# main_flight_computer.net
KiCad netlist of a schematic drawn in EAGLE
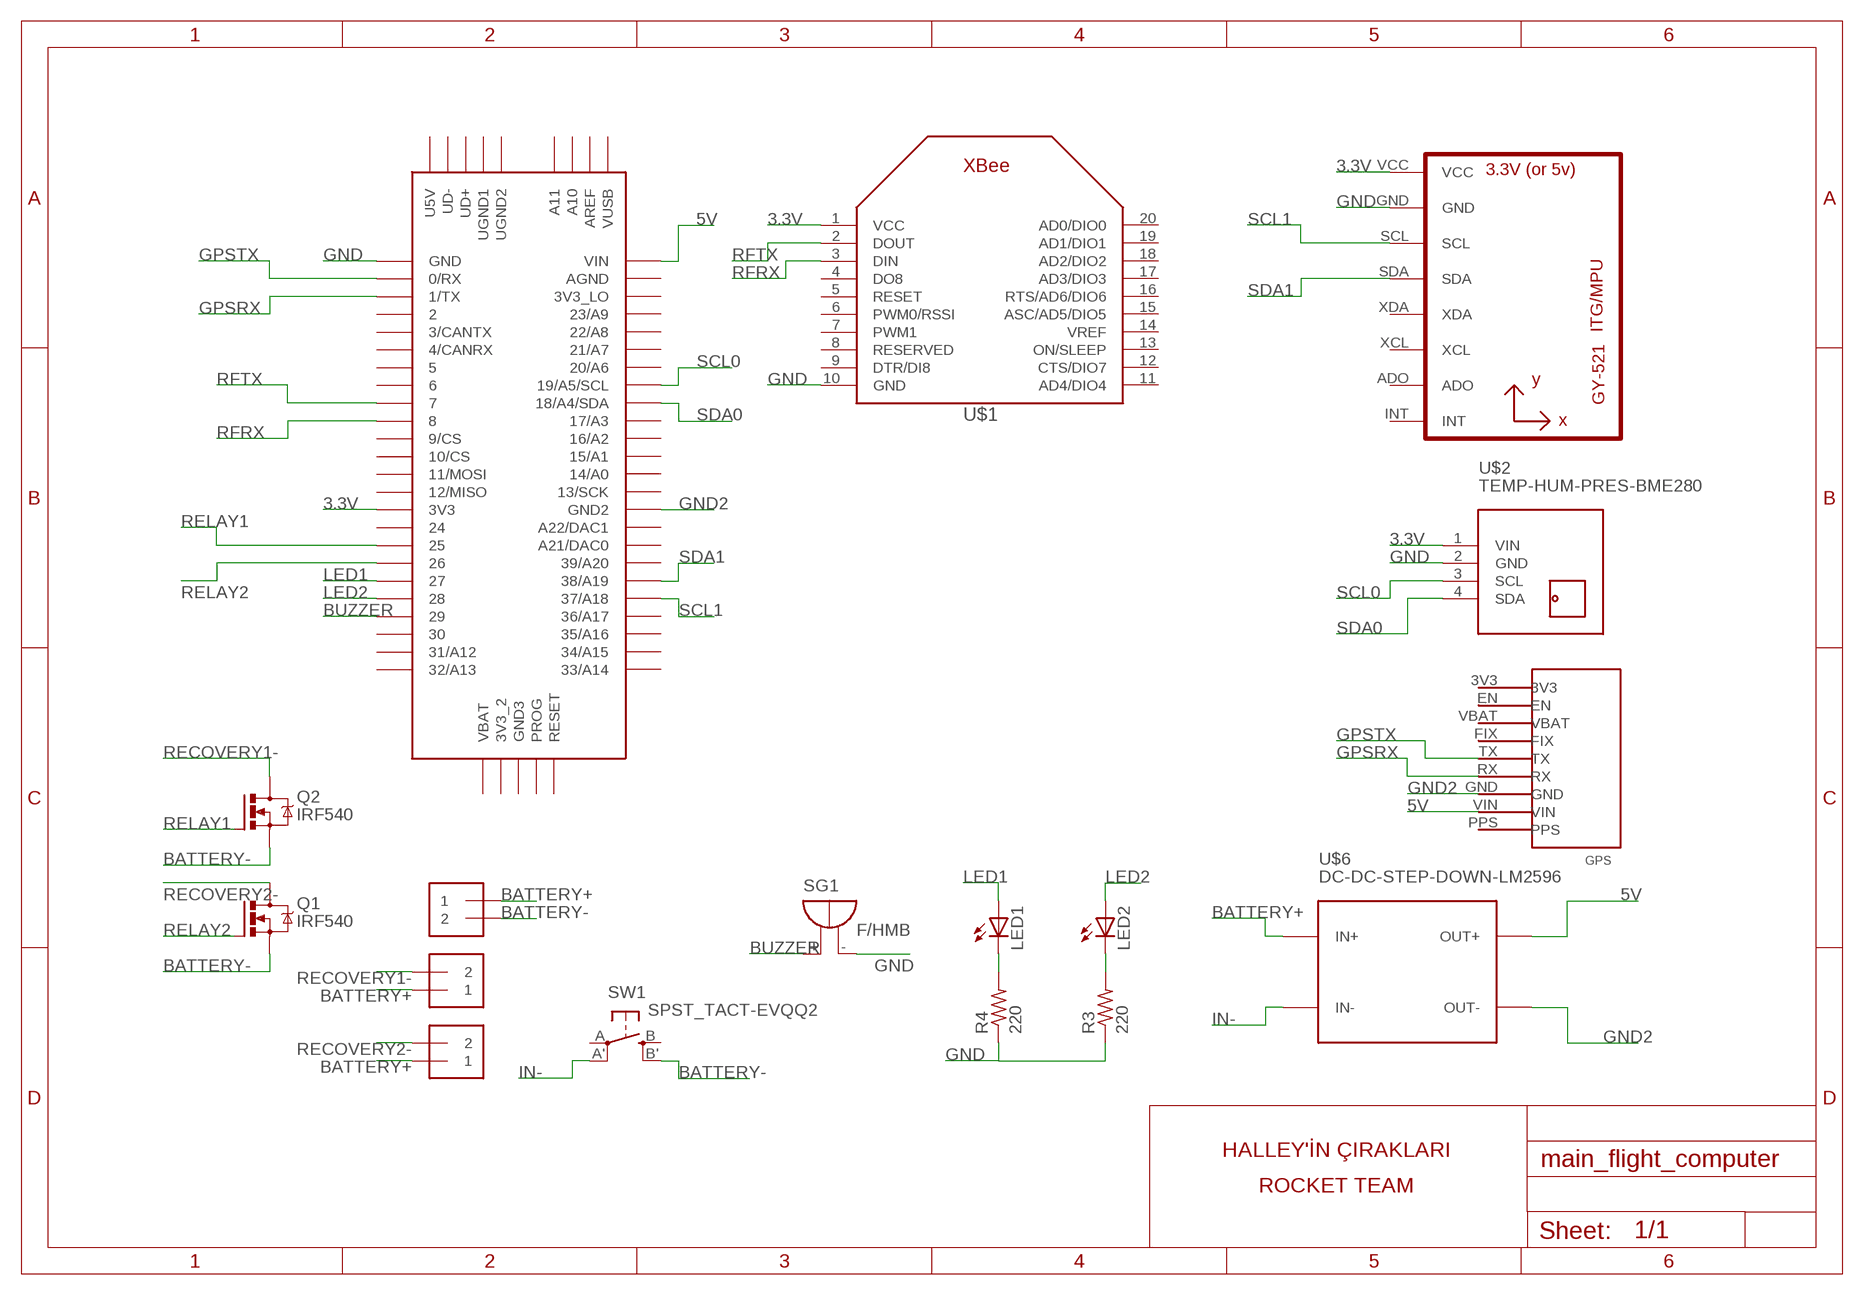
[diagram p0: schematic, sheet 1]

(export (version "E")
  (design (tool "Eeschema 10.0.6"))
  (components
    (comp (ref "J1")
      (value "1X2-3.5MM")
      (footprint "eagle-import:1X2-3.5MM")
      (libsource (lib "eagle-import") (part "1X2-3.5MM"))
    )
    (comp (ref "J2")
      (value "1X2-3.5MM")
      (footprint "eagle-import:1X2-3.5MM")
      (libsource (lib "eagle-import") (part "1X2-3.5MM"))
    )
    (comp (ref "J3")
      (value "1X2-3.5MM")
      (footprint "eagle-import:1X2-3.5MM")
      (libsource (lib "eagle-import") (part "1X2-3.5MM"))
    )
    (comp (ref "LED1")
      (value "LED5MM")
      (footprint "eagle-import:LED5MM")
      (libsource (lib "eagle-import") (part "LED5MM"))
    )
    (comp (ref "LED2")
      (value "LED5MM")
      (footprint "eagle-import:LED5MM")
      (libsource (lib "eagle-import") (part "LED5MM"))
    )
    (comp (ref "Q1")
      (value "IRF540")
      (footprint "eagle-import:TO220BV")
      (fields (field (name "MANUFACTURER") "Infineon Technologies") (field (name "MPN") "IRF540NPBF"))
      (libsource (lib "eagle-import") (part "NMOSFET_-TO220IRF540"))
    )
    (comp (ref "Q2")
      (value "IRF540")
      (footprint "eagle-import:TO220BV")
      (fields (field (name "MANUFACTURER") "Infineon Technologies") (field (name "MPN") "IRF540NPBF"))
      (libsource (lib "eagle-import") (part "NMOSFET_-TO220IRF540"))
    )
    (comp (ref "R3")
      (value "220")
      (footprint "eagle-import:0204_7")
      (libsource (lib "eagle-import") (part "R-US_0204/7"))
    )
    (comp (ref "R4")
      (value "220")
      (footprint "eagle-import:0204_7")
      (libsource (lib "eagle-import") (part "R-US_0204/7"))
    )
    (comp (ref "SG1")
      (value "F/HMB")
      (footprint "eagle-import:F_HMB")
      (libsource (lib "eagle-import") (part "F/HMB"))
    )
    (comp (ref "SW1")
      (value "SPST_TACT-EVQQ2")
      (footprint "eagle-import:EVQ-Q2")
      (libsource (lib "eagle-import") (part "SPST_TACT-EVQQ2"))
    )
    (comp (ref "U$1")
      (value "XBEE")
      (footprint "eagle-import:XBEE")
      (libsource (lib "eagle-import") (part "XBEE"))
    )
    (comp (ref "U$2")
      (value "TEMP-HUM-PRES-BME280")
      (footprint "eagle-import:TEMP-HUM-PRES-BME280")
      (libsource (lib "eagle-import") (part "TEMP-HUM-PRES-BME280"))
    )
    (comp (ref "U$3")
      (value "TEENSY_3.5/3.6")
      (footprint "eagle-import:TEENSY_3.5_3.6")
      (libsource (lib "eagle-import") (part "TEENSY_3.5/3.6"))
    )
    (comp (ref "U$5")
      (value "GPS")
      (footprint "eagle-import:GPS")
      (libsource (lib "eagle-import") (part "GPS"))
    )
    (comp (ref "U$6")
      (value "DC-DC-STEP-DOWN-LM2596")
      (footprint "eagle-import:DC-DC-STEP-DOWN-LM2596")
      (libsource (lib "eagle-import") (part "DC-DC-STEP-DOWN-LM2596"))
    )
    (comp (ref "U1")
      (value "GY-521MPU6050")
      (footprint "eagle-import:GY-521")
      (libsource (lib "eagle-import") (part "GY-521MPU6050"))
    )
  )
  (nets
    (net (code "1") (name "/3.3V") (class "Default")
      (node (ref "U$1") (pin "1") (pinfunction "VCC_1") (pintype "power_in"))
      (node (ref "U$2") (pin "1") (pinfunction "VIN_1") (pintype "power_in"))
      (node (ref "U$3") (pin "3V3") (pinfunction "3V3_3V3") (pintype "bidirectional"))
      (node (ref "U1") (pin "VCC") (pinfunction "VCC_VCC") (pintype "bidirectional"))
    )
    (net (code "2") (name "/5V") (class "Default")
      (node (ref "U$3") (pin "VIN") (pinfunction "VIN_VIN") (pintype "bidirectional"))
      (node (ref "U$5") (pin "VIN") (pinfunction "VIN_VIN") (pintype "bidirectional"))
      (node (ref "U$6") (pin "OUT+") (pinfunction "OUT+_OUT+") (pintype "bidirectional"))
    )
    (net (code "3") (name "/BATTERY+") (class "Default")
      (node (ref "J1") (pin "1") (pinfunction "1_1") (pintype "passive"))
      (node (ref "J2") (pin "1") (pinfunction "1_1") (pintype "passive"))
      (node (ref "J3") (pin "1") (pinfunction "1_1") (pintype "passive"))
      (node (ref "U$6") (pin "IN+") (pinfunction "IN+_IN+") (pintype "bidirectional"))
    )
    (net (code "4") (name "/BATTERY-") (class "Default")
      (node (ref "J1") (pin "2") (pinfunction "2_2") (pintype "passive"))
      (node (ref "Q1") (pin "S") (pinfunction "S_S") (pintype "passive"))
      (node (ref "Q2") (pin "S") (pinfunction "S_S") (pintype "passive"))
      (node (ref "SW1") (pin "B'") (pinfunction "S1_B'") (pintype "passive"))
    )
    (net (code "5") (name "/BUZZER") (class "Default")
      (node (ref "SG1") (pin "+") (pinfunction "+_+") (pintype "passive"))
      (node (ref "U$3") (pin "29") (pinfunction "29_29") (pintype "bidirectional"))
    )
    (net (code "6") (name "/GND") (class "Default")
      (node (ref "R3") (pin "1") (pinfunction "1_1") (pintype "passive"))
      (node (ref "R4") (pin "1") (pinfunction "1_1") (pintype "passive"))
      (node (ref "SG1") (pin "-") (pinfunction "-_-") (pintype "passive"))
      (node (ref "U$1") (pin "10") (pinfunction "GND_10") (pintype "power_in"))
      (node (ref "U$2") (pin "2") (pinfunction "GND_2") (pintype "power_in"))
      (node (ref "U$3") (pin "GND") (pinfunction "GND_GND") (pintype "bidirectional"))
      (node (ref "U1") (pin "GND") (pinfunction "GND_GND") (pintype "bidirectional"))
    )
    (net (code "7") (name "/GND2") (class "Default")
      (node (ref "U$3") (pin "GND2") (pinfunction "GND2_GND2") (pintype "bidirectional"))
      (node (ref "U$5") (pin "GND") (pinfunction "GND_GND") (pintype "bidirectional"))
      (node (ref "U$6") (pin "OUT-") (pinfunction "OUT-_OUT-") (pintype "bidirectional"))
    )
    (net (code "8") (name "/GPSRX") (class "Default")
      (node (ref "U$3") (pin "1/TX") (pinfunction "1/TX_1/TX") (pintype "bidirectional"))
      (node (ref "U$5") (pin "RX") (pinfunction "RX_RX") (pintype "bidirectional"))
    )
    (net (code "9") (name "/GPSTX") (class "Default")
      (node (ref "U$3") (pin "0/RX") (pinfunction "0/RX_0/RX") (pintype "bidirectional"))
      (node (ref "U$5") (pin "TX") (pinfunction "TX_TX") (pintype "bidirectional"))
    )
    (net (code "10") (name "/IN-") (class "Default")
      (node (ref "SW1") (pin "A'") (pinfunction "P1_A'") (pintype "passive"))
      (node (ref "U$6") (pin "IN-") (pinfunction "IN-_IN-") (pintype "bidirectional"))
    )
    (net (code "11") (name "/LED1") (class "Default")
      (node (ref "LED1") (pin "A") (pinfunction "A_A") (pintype "passive"))
      (node (ref "U$3") (pin "27") (pinfunction "27_27") (pintype "bidirectional"))
    )
    (net (code "12") (name "/LED2") (class "Default")
      (node (ref "LED2") (pin "A") (pinfunction "A_A") (pintype "passive"))
      (node (ref "U$3") (pin "28") (pinfunction "28_28") (pintype "bidirectional"))
    )
    (net (code "13") (name "/RECOVERY1-") (class "Default")
      (node (ref "J2") (pin "2") (pinfunction "2_2") (pintype "passive"))
      (node (ref "Q2") (pin "D") (pinfunction "D_D") (pintype "passive"))
    )
    (net (code "14") (name "/RECOVERY2-") (class "Default")
      (node (ref "J3") (pin "2") (pinfunction "2_2") (pintype "passive"))
      (node (ref "Q1") (pin "D") (pinfunction "D_D") (pintype "passive"))
    )
    (net (code "15") (name "/RELAY1") (class "Default")
      (node (ref "Q2") (pin "G") (pinfunction "G_G") (pintype "passive"))
      (node (ref "U$3") (pin "25") (pinfunction "25_25") (pintype "bidirectional"))
    )
    (net (code "16") (name "/RELAY2") (class "Default")
      (node (ref "Q1") (pin "G") (pinfunction "G_G") (pintype "passive"))
      (node (ref "U$3") (pin "26") (pinfunction "26_26") (pintype "bidirectional"))
    )
    (net (code "17") (name "/RFRX") (class "Default")
      (node (ref "U$1") (pin "3") (pinfunction "DIN_3") (pintype "input"))
      (node (ref "U$3") (pin "8") (pinfunction "8_8") (pintype "bidirectional"))
    )
    (net (code "18") (name "/RFTX") (class "Default")
      (node (ref "U$1") (pin "2") (pinfunction "DOUT_2") (pintype "output"))
      (node (ref "U$3") (pin "7") (pinfunction "7_7") (pintype "bidirectional"))
    )
    (net (code "19") (name "/SCL0") (class "Default")
      (node (ref "U$2") (pin "3") (pinfunction "SCL_3") (pintype "bidirectional"))
      (node (ref "U$3") (pin "19/A5/SCL") (pinfunction "19/A5/SCL_19/A5/SCL") (pintype "bidirectional"))
    )
    (net (code "20") (name "/SCL1") (class "Default")
      (node (ref "U$3") (pin "37/A18") (pinfunction "37/A18_37/A18") (pintype "bidirectional"))
      (node (ref "U1") (pin "SCL") (pinfunction "SCL_SCL") (pintype "bidirectional"))
    )
    (net (code "21") (name "/SDA0") (class "Default")
      (node (ref "U$2") (pin "4") (pinfunction "SDA_4") (pintype "bidirectional"))
      (node (ref "U$3") (pin "18/A4/SDA") (pinfunction "18/A4/SDA_18/A4/SDA") (pintype "bidirectional"))
    )
    (net (code "22") (name "/SDA1") (class "Default")
      (node (ref "U$3") (pin "38/A19") (pinfunction "38/A19_38/A19") (pintype "bidirectional"))
      (node (ref "U1") (pin "SDA") (pinfunction "SDA_SDA") (pintype "bidirectional"))
    )
    (net (code "23") (name "Net-(LED1-C)") (class "Default")
      (node (ref "LED1") (pin "K") (pinfunction "C_K") (pintype "passive"))
      (node (ref "R4") (pin "2") (pinfunction "2_2") (pintype "passive"))
    )
    (net (code "24") (name "Net-(LED2-C)") (class "Default")
      (node (ref "LED2") (pin "K") (pinfunction "C_K") (pintype "passive"))
      (node (ref "R3") (pin "2") (pinfunction "2_2") (pintype "passive"))
    )
    (net (code "25") (name "unconnected-(SW1-P-PadA)") (class "Default")
      (node (ref "SW1") (pin "A") (pinfunction "P_A") (pintype "passive"))
    )
    (net (code "26") (name "unconnected-(SW1-S-PadB)") (class "Default")
      (node (ref "SW1") (pin "B") (pinfunction "S_B") (pintype "passive"))
    )
    (net (code "27") (name "unconnected-(U$1-AD0{slash}DIO0-Pad20)") (class "Default")
      (node (ref "U$1") (pin "20") (pinfunction "AD0/DIO0_20") (pintype "bidirectional"))
    )
    (net (code "28") (name "unconnected-(U$1-AD1{slash}DIO1-Pad19)") (class "Default")
      (node (ref "U$1") (pin "19") (pinfunction "AD1/DIO1_19") (pintype "bidirectional"))
    )
    (net (code "29") (name "unconnected-(U$1-AD2{slash}DIO2-Pad18)") (class "Default")
      (node (ref "U$1") (pin "18") (pinfunction "AD2/DIO2_18") (pintype "bidirectional"))
    )
    (net (code "30") (name "unconnected-(U$1-AD3{slash}DIO3-Pad17)") (class "Default")
      (node (ref "U$1") (pin "17") (pinfunction "AD3/DIO3_17") (pintype "bidirectional"))
    )
    (net (code "31") (name "unconnected-(U$1-AD4{slash}DIO4-Pad11)") (class "Default")
      (node (ref "U$1") (pin "11") (pinfunction "AD4/DIO4_11") (pintype "bidirectional"))
    )
    (net (code "32") (name "unconnected-(U$1-ASC{slash}AD5{slash}DIO5-Pad15)") (class "Default")
      (node (ref "U$1") (pin "15") (pinfunction "ASC/AD5/DIO5_15") (pintype "bidirectional"))
    )
    (net (code "33") (name "unconnected-(U$1-CTS{slash}DIO7-Pad12)") (class "Default")
      (node (ref "U$1") (pin "12") (pinfunction "CTS/DIO7_12") (pintype "bidirectional"))
    )
    (net (code "34") (name "unconnected-(U$1-DO8-Pad4)") (class "Default")
      (node (ref "U$1") (pin "4") (pinfunction "DO8_4") (pintype "output"))
    )
    (net (code "35") (name "unconnected-(U$1-DTR{slash}DI8-Pad9)") (class "Default")
      (node (ref "U$1") (pin "9") (pinfunction "DTR/DI8_9") (pintype "input"))
    )
    (net (code "36") (name "unconnected-(U$1-ON{slash}SLEEP-Pad13)") (class "Default")
      (node (ref "U$1") (pin "13") (pinfunction "ON/SLEEP_13") (pintype "output"))
    )
    (net (code "37") (name "unconnected-(U$1-PWM0{slash}RSSI-Pad6)") (class "Default")
      (node (ref "U$1") (pin "6") (pinfunction "PWM0/RSSI_6") (pintype "output"))
    )
    (net (code "38") (name "unconnected-(U$1-PWM1-Pad7)") (class "Default")
      (node (ref "U$1") (pin "7") (pinfunction "PWM1_7") (pintype "output"))
    )
    (net (code "39") (name "unconnected-(U$1-RESERVED-Pad8)") (class "Default")
      (node (ref "U$1") (pin "8") (pinfunction "RESERVED_8") (pintype "no_connect"))
    )
    (net (code "40") (name "unconnected-(U$1-RESET-Pad5)") (class "Default")
      (node (ref "U$1") (pin "5") (pinfunction "RESET_5") (pintype "input"))
    )
    (net (code "41") (name "unconnected-(U$1-RTS{slash}AD6{slash}DIO6-Pad16)") (class "Default")
      (node (ref "U$1") (pin "16") (pinfunction "RTS/AD6/DIO6_16") (pintype "bidirectional"))
    )
    (net (code "42") (name "unconnected-(U$1-VREF-Pad14)") (class "Default")
      (node (ref "U$1") (pin "14") (pinfunction "VREF_14") (pintype "input"))
    )
    (net (code "43") (name "unconnected-(U$3-A21{slash}DAC0-Pad21{slash}DAC0)") (class "Default")
      (node (ref "U$3") (pin "21/DAC0") (pinfunction "A21/DAC0_21/DAC0") (pintype "bidirectional"))
    )
    (net (code "44") (name "unconnected-(U$3-Pad2)") (class "Default")
      (node (ref "U$3") (pin "2") (pinfunction "2_2") (pintype "bidirectional"))
    )
    (net (code "45") (name "unconnected-(U$3-Pad3V3_2)") (class "Default")
      (node (ref "U$3") (pin "3V3_2") (pinfunction "3V3_2_3V3_2") (pintype "bidirectional"))
    )
    (net (code "46") (name "unconnected-(U$3-Pad3V3_LO)") (class "Default")
      (node (ref "U$3") (pin "3V3_LO") (pinfunction "3V3_LO_3V3_LO") (pintype "bidirectional"))
    )
    (net (code "47") (name "unconnected-(U$3-Pad3{slash}CANTX)") (class "Default")
      (node (ref "U$3") (pin "3/CANTX") (pinfunction "3/CANTX_3/CANTX") (pintype "bidirectional"))
    )
    (net (code "48") (name "unconnected-(U$3-Pad4{slash}CANRX)") (class "Default")
      (node (ref "U$3") (pin "4/CANRX") (pinfunction "4/CANRX_4/CANRX") (pintype "bidirectional"))
    )
    (net (code "49") (name "unconnected-(U$3-Pad5)") (class "Default")
      (node (ref "U$3") (pin "5") (pinfunction "5_5") (pintype "bidirectional"))
    )
    (net (code "50") (name "unconnected-(U$3-Pad6)") (class "Default")
      (node (ref "U$3") (pin "6") (pinfunction "6_6") (pintype "bidirectional"))
    )
    (net (code "51") (name "unconnected-(U$3-Pad9{slash}CS)") (class "Default")
      (node (ref "U$3") (pin "9/CS") (pinfunction "9/CS_9/CS") (pintype "bidirectional"))
    )
    (net (code "52") (name "unconnected-(U$3-Pad10{slash}CS)") (class "Default")
      (node (ref "U$3") (pin "10/CS") (pinfunction "10/CS_10/CS") (pintype "bidirectional"))
    )
    (net (code "53") (name "unconnected-(U$3-Pad11{slash}MOSI)") (class "Default")
      (node (ref "U$3") (pin "11/MOSI") (pinfunction "11/MOSI_11/MOSI") (pintype "bidirectional"))
    )
    (net (code "54") (name "unconnected-(U$3-Pad12{slash}MISO)") (class "Default")
      (node (ref "U$3") (pin "12/MISO") (pinfunction "12/MISO_12/MISO") (pintype "bidirectional"))
    )
    (net (code "55") (name "unconnected-(U$3-Pad13{slash}SCK)") (class "Default")
      (node (ref "U$3") (pin "13/SCK") (pinfunction "13/SCK_13/SCK") (pintype "bidirectional"))
    )
    (net (code "56") (name "unconnected-(U$3-Pad14{slash}A0)") (class "Default")
      (node (ref "U$3") (pin "14/A0") (pinfunction "14/A0_14/A0") (pintype "bidirectional"))
    )
    (net (code "57") (name "unconnected-(U$3-Pad15{slash}A1)") (class "Default")
      (node (ref "U$3") (pin "15/A1") (pinfunction "15/A1_15/A1") (pintype "bidirectional"))
    )
    (net (code "58") (name "unconnected-(U$3-Pad16{slash}A2)") (class "Default")
      (node (ref "U$3") (pin "16/A2") (pinfunction "16/A2_16/A2") (pintype "bidirectional"))
    )
    (net (code "59") (name "unconnected-(U$3-Pad17{slash}A3)") (class "Default")
      (node (ref "U$3") (pin "17/A3") (pinfunction "17/A3_17/A3") (pintype "bidirectional"))
    )
    (net (code "60") (name "unconnected-(U$3-Pad20{slash}A6)") (class "Default")
      (node (ref "U$3") (pin "20/A6") (pinfunction "20/A6_20/A6") (pintype "bidirectional"))
    )
    (net (code "61") (name "unconnected-(U$3-Pad21{slash}A7)") (class "Default")
      (node (ref "U$3") (pin "21/A7") (pinfunction "21/A7_21/A7") (pintype "bidirectional"))
    )
    (net (code "62") (name "unconnected-(U$3-Pad22{slash}A8)") (class "Default")
      (node (ref "U$3") (pin "22/A8") (pinfunction "22/A8_22/A8") (pintype "bidirectional"))
    )
    (net (code "63") (name "unconnected-(U$3-Pad23{slash}A9)") (class "Default")
      (node (ref "U$3") (pin "23/A9") (pinfunction "23/A9_23/A9") (pintype "bidirectional"))
    )
    (net (code "64") (name "unconnected-(U$3-Pad24)") (class "Default")
      (node (ref "U$3") (pin "24") (pinfunction "24_24") (pintype "bidirectional"))
    )
    (net (code "65") (name "unconnected-(U$3-Pad30)") (class "Default")
      (node (ref "U$3") (pin "30") (pinfunction "30_30") (pintype "bidirectional"))
    )
    (net (code "66") (name "unconnected-(U$3-Pad31{slash}A12)") (class "Default")
      (node (ref "U$3") (pin "31/A12") (pinfunction "31/A12_31/A12") (pintype "bidirectional"))
    )
    (net (code "67") (name "unconnected-(U$3-Pad32{slash}A13)") (class "Default")
      (node (ref "U$3") (pin "32/A13") (pinfunction "32/A13_32/A13") (pintype "bidirectional"))
    )
    (net (code "68") (name "unconnected-(U$3-Pad33{slash}A14)") (class "Default")
      (node (ref "U$3") (pin "33/A14") (pinfunction "33/A14_33/A14") (pintype "bidirectional"))
    )
    (net (code "69") (name "unconnected-(U$3-Pad34{slash}A15)") (class "Default")
      (node (ref "U$3") (pin "34/A15") (pinfunction "34/A15_34/A15") (pintype "bidirectional"))
    )
    (net (code "70") (name "unconnected-(U$3-Pad35{slash}A16)") (class "Default")
      (node (ref "U$3") (pin "35/A16") (pinfunction "35/A16_35/A16") (pintype "bidirectional"))
    )
    (net (code "71") (name "unconnected-(U$3-Pad36{slash}A17)") (class "Default")
      (node (ref "U$3") (pin "36/A17") (pinfunction "36/A17_36/A17") (pintype "bidirectional"))
    )
    (net (code "72") (name "unconnected-(U$3-Pad39{slash}A20)") (class "Default")
      (node (ref "U$3") (pin "39/A20") (pinfunction "39/A20_39/A20") (pintype "bidirectional"))
    )
    (net (code "73") (name "unconnected-(U$3-PadA10)") (class "Default")
      (node (ref "U$3") (pin "A10") (pinfunction "A10_A10") (pintype "bidirectional"))
    )
    (net (code "74") (name "unconnected-(U$3-PadA11)") (class "Default")
      (node (ref "U$3") (pin "A11") (pinfunction "A11_A11") (pintype "bidirectional"))
    )
    (net (code "75") (name "unconnected-(U$3-PadA22{slash}DAC1)") (class "Default")
      (node (ref "U$3") (pin "A22/DAC1") (pinfunction "A22/DAC1_A22/DAC1") (pintype "bidirectional"))
    )
    (net (code "76") (name "unconnected-(U$3-PadAGND)") (class "Default")
      (node (ref "U$3") (pin "AGND") (pinfunction "AGND_AGND") (pintype "bidirectional"))
    )
    (net (code "77") (name "unconnected-(U$3-PadAREF)") (class "Default")
      (node (ref "U$3") (pin "AREF") (pinfunction "AREF_AREF") (pintype "bidirectional"))
    )
    (net (code "78") (name "unconnected-(U$3-PadGND3)") (class "Default")
      (node (ref "U$3") (pin "GND3") (pinfunction "GND3_GND3") (pintype "bidirectional"))
    )
    (net (code "79") (name "unconnected-(U$3-PadPROG)") (class "Default")
      (node (ref "U$3") (pin "PROG") (pinfunction "PROG_PROG") (pintype "bidirectional"))
    )
    (net (code "80") (name "unconnected-(U$3-PadRESET)") (class "Default")
      (node (ref "U$3") (pin "RESET") (pinfunction "RESET_RESET") (pintype "bidirectional"))
    )
    (net (code "81") (name "unconnected-(U$3-PadU5V)") (class "Default")
      (node (ref "U$3") (pin "U5V") (pinfunction "U5V_U5V") (pintype "bidirectional"))
    )
    (net (code "82") (name "unconnected-(U$3-PadUD+)") (class "Default")
      (node (ref "U$3") (pin "UD+") (pinfunction "UD+_UD+") (pintype "bidirectional"))
    )
    (net (code "83") (name "unconnected-(U$3-PadUD-)") (class "Default")
      (node (ref "U$3") (pin "UD-") (pinfunction "UD-_UD-") (pintype "bidirectional"))
    )
    (net (code "84") (name "unconnected-(U$3-PadUGND1)") (class "Default")
      (node (ref "U$3") (pin "UGND1") (pinfunction "UGND1_UGND1") (pintype "bidirectional"))
    )
    (net (code "85") (name "unconnected-(U$3-PadUGND2)") (class "Default")
      (node (ref "U$3") (pin "UGND2") (pinfunction "UGND2_UGND2") (pintype "bidirectional"))
    )
    (net (code "86") (name "unconnected-(U$3-PadVBAT)") (class "Default")
      (node (ref "U$3") (pin "VBAT") (pinfunction "VBAT_VBAT") (pintype "bidirectional"))
    )
    (net (code "87") (name "unconnected-(U$3-PadVUSB)") (class "Default")
      (node (ref "U$3") (pin "VUSB") (pinfunction "VUSB_VUSB") (pintype "bidirectional"))
    )
    (net (code "88") (name "unconnected-(U$5-Pad3V3)") (class "Default")
      (node (ref "U$5") (pin "3V3") (pinfunction "3V3_3V3") (pintype "bidirectional"))
    )
    (net (code "89") (name "unconnected-(U$5-PadEN)") (class "Default")
      (node (ref "U$5") (pin "EN") (pinfunction "EN_EN") (pintype "bidirectional"))
    )
    (net (code "90") (name "unconnected-(U$5-PadFIX)") (class "Default")
      (node (ref "U$5") (pin "FIX") (pinfunction "FIX_FIX") (pintype "bidirectional"))
    )
    (net (code "91") (name "unconnected-(U$5-PadPPS)") (class "Default")
      (node (ref "U$5") (pin "PPS") (pinfunction "PPS_PPS") (pintype "bidirectional"))
    )
    (net (code "92") (name "unconnected-(U$5-PadVBAT)") (class "Default")
      (node (ref "U$5") (pin "VBAT") (pinfunction "VBAT_VBAT") (pintype "bidirectional"))
    )
    (net (code "93") (name "unconnected-(U1-PadADO)") (class "Default")
      (node (ref "U1") (pin "ADO") (pinfunction "ADO_ADO") (pintype "bidirectional"))
    )
    (net (code "94") (name "unconnected-(U1-PadINT)") (class "Default")
      (node (ref "U1") (pin "INT") (pinfunction "INT_INT") (pintype "bidirectional"))
    )
    (net (code "95") (name "unconnected-(U1-PadXCL)") (class "Default")
      (node (ref "U1") (pin "XCL") (pinfunction "XCL_XCL") (pintype "bidirectional"))
    )
    (net (code "96") (name "unconnected-(U1-PadXDA)") (class "Default")
      (node (ref "U1") (pin "XDA") (pinfunction "XDA_XDA") (pintype "bidirectional"))
    )
  )
)
